# HCI.net
KiCad netlist of a schematic drawn in Altium Designer
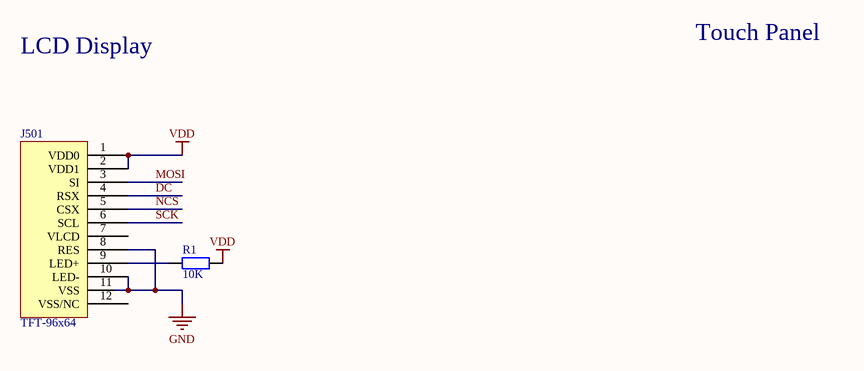
[diagram p0: HCI.SchDoc]

(export (version "E")
  (design (tool "Eeschema 10.0.6"))
  (components
    (comp (ref "J501")
      (value "TFT-96x64")
      (footprint "TFT-PIN12-0.5")
      (libsource (lib "Misc") (part "TFT-96x64"))
    )
    (comp (ref "R1")
      (value "10K")
      (footprint "0603M")
      (description "Resistor")
      (fields (field (name "PUBLISHER") "Altium Limited"))
      (libsource (lib "Miscellaneous Devices") (part "Res2"))
    )
  )
  (nets
    (net (code "1") (name "/DC") (class "Default")
      (node (ref "J501") (pin "4") (pinfunction "RSX_4") (pintype "passive"))
    )
    (net (code "2") (name "/MOSI") (class "Default")
      (node (ref "J501") (pin "3") (pinfunction "SI_3") (pintype "passive"))
    )
    (net (code "3") (name "/NCS") (class "Default")
      (node (ref "J501") (pin "5") (pinfunction "CSX_5") (pintype "passive"))
    )
    (net (code "4") (name "/SCK") (class "Default")
      (node (ref "J501") (pin "6") (pinfunction "SCL_6") (pintype "passive"))
    )
    (net (code "5") (name "GND") (class "Default")
      (node (ref "J501") (pin "10") (pinfunction "LED-_10") (pintype "passive"))
      (node (ref "J501") (pin "11") (pinfunction "VSS_11") (pintype "passive"))
      (node (ref "J501") (pin "8") (pinfunction "RES_8") (pintype "passive"))
    )
    (net (code "6") (name "Net-(J501-LED+)") (class "Default")
      (node (ref "J501") (pin "9") (pinfunction "LED+_9") (pintype "passive"))
      (node (ref "R1") (pin "1") (pinfunction "1_1") (pintype "passive"))
    )
    (net (code "7") (name "VDD") (class "Default")
      (node (ref "J501") (pin "1") (pinfunction "VDD0_1") (pintype "passive"))
      (node (ref "J501") (pin "2") (pinfunction "VDD1_2") (pintype "passive"))
      (node (ref "R1") (pin "2") (pinfunction "2_2") (pintype "passive"))
    )
    (net (code "8") (name "unconnected-(J501-VLCD-Pad7)") (class "Default")
      (node (ref "J501") (pin "7") (pinfunction "VLCD_7") (pintype "passive"))
    )
    (net (code "9") (name "unconnected-(J501-VSS{slash}NC-Pad12)") (class "Default")
      (node (ref "J501") (pin "12") (pinfunction "VSS/NC_12") (pintype "passive"))
    )
  )
)
